# teensy_3-6sch.net
KiCad netlist of a schematic drawn in EAGLE
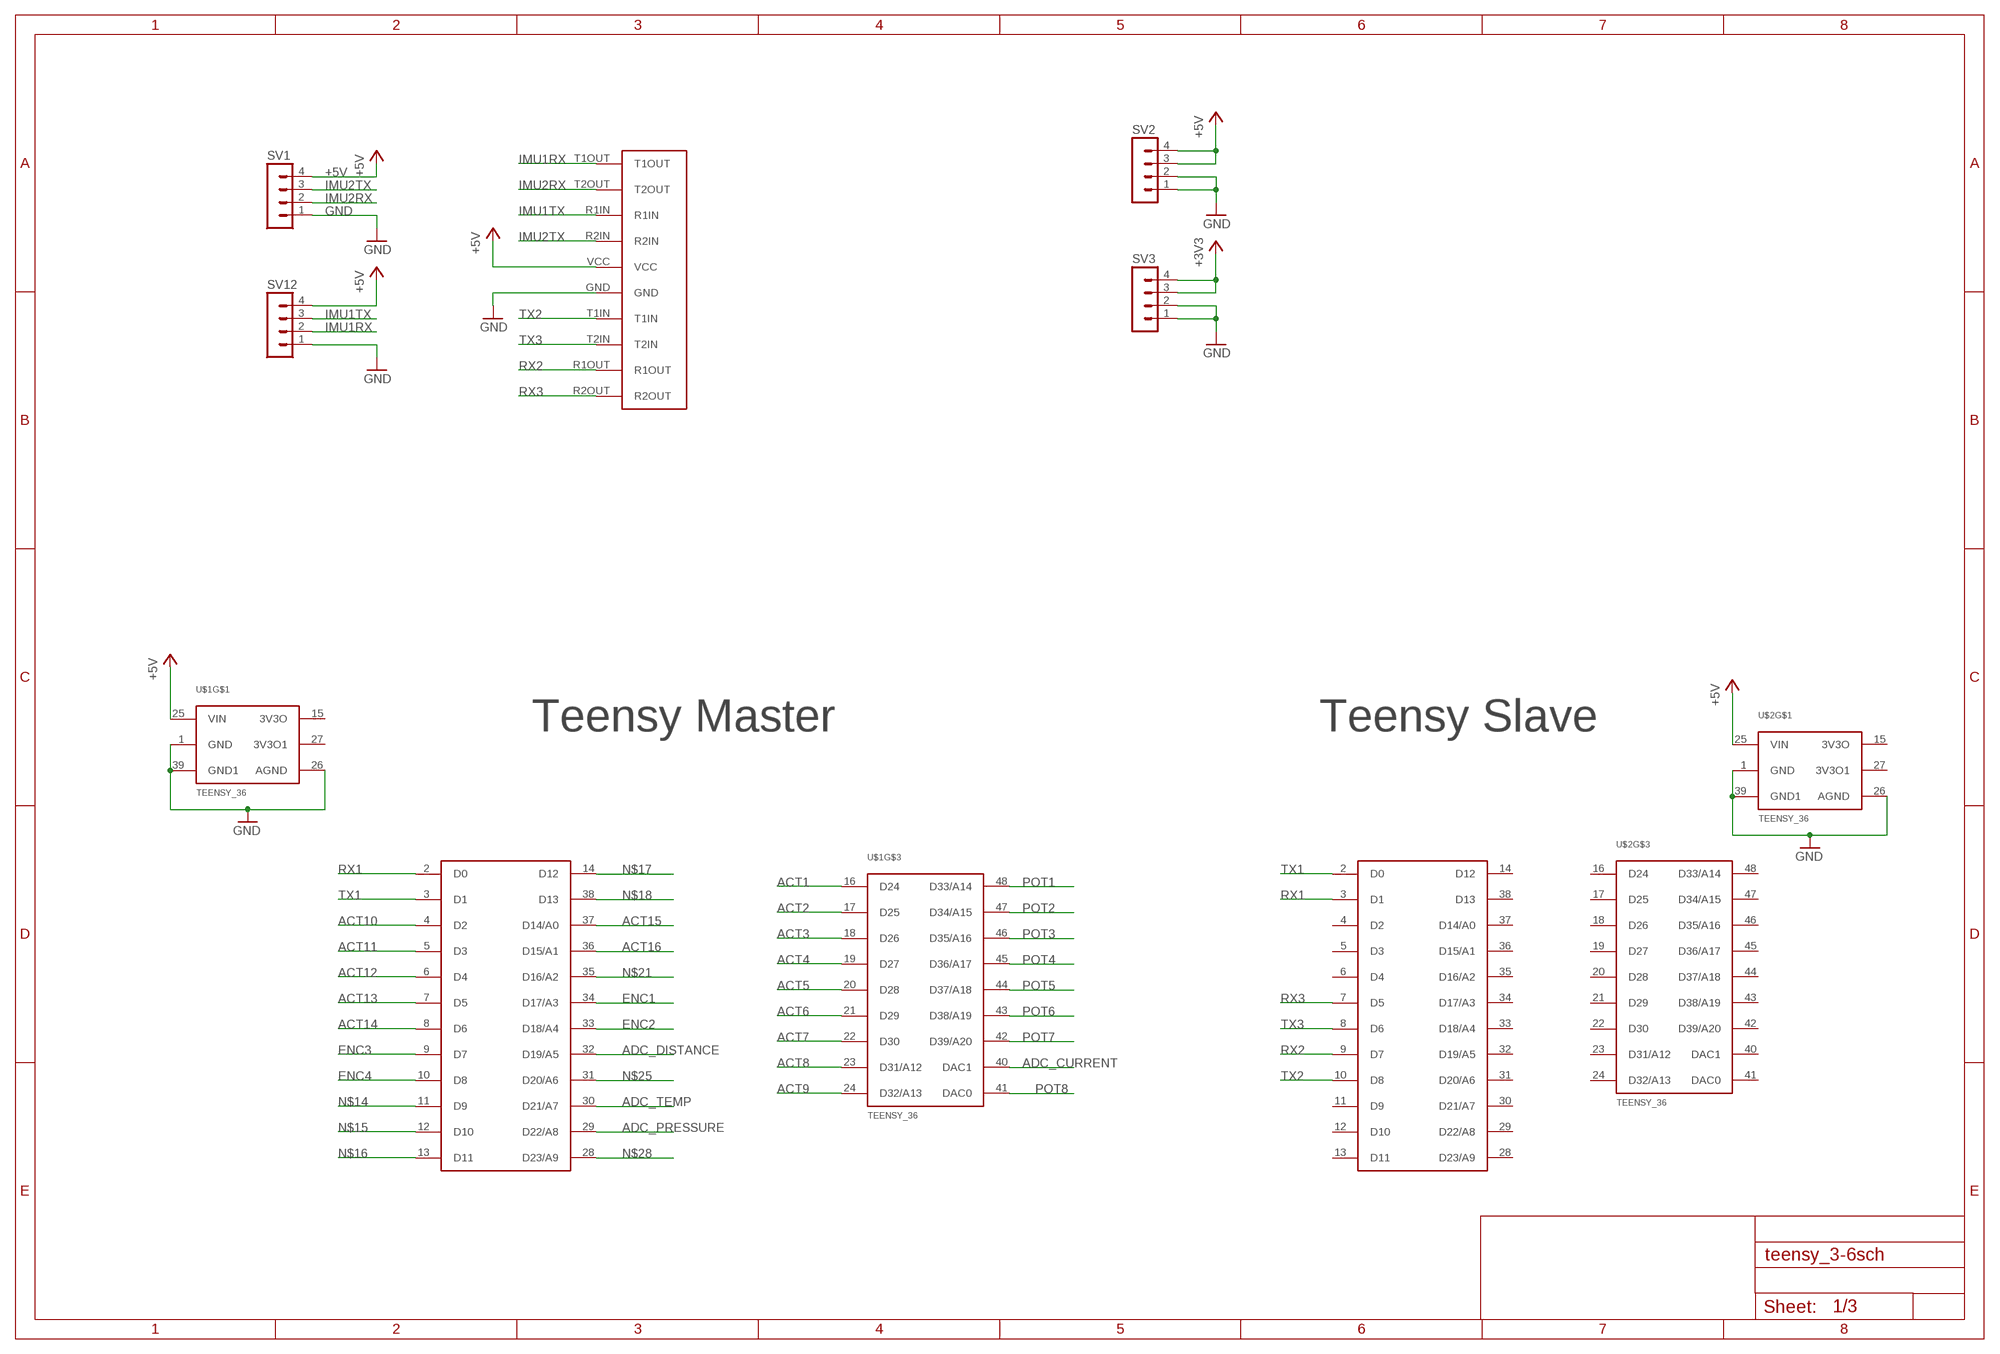
[diagram p0: schematic, sheet 1]
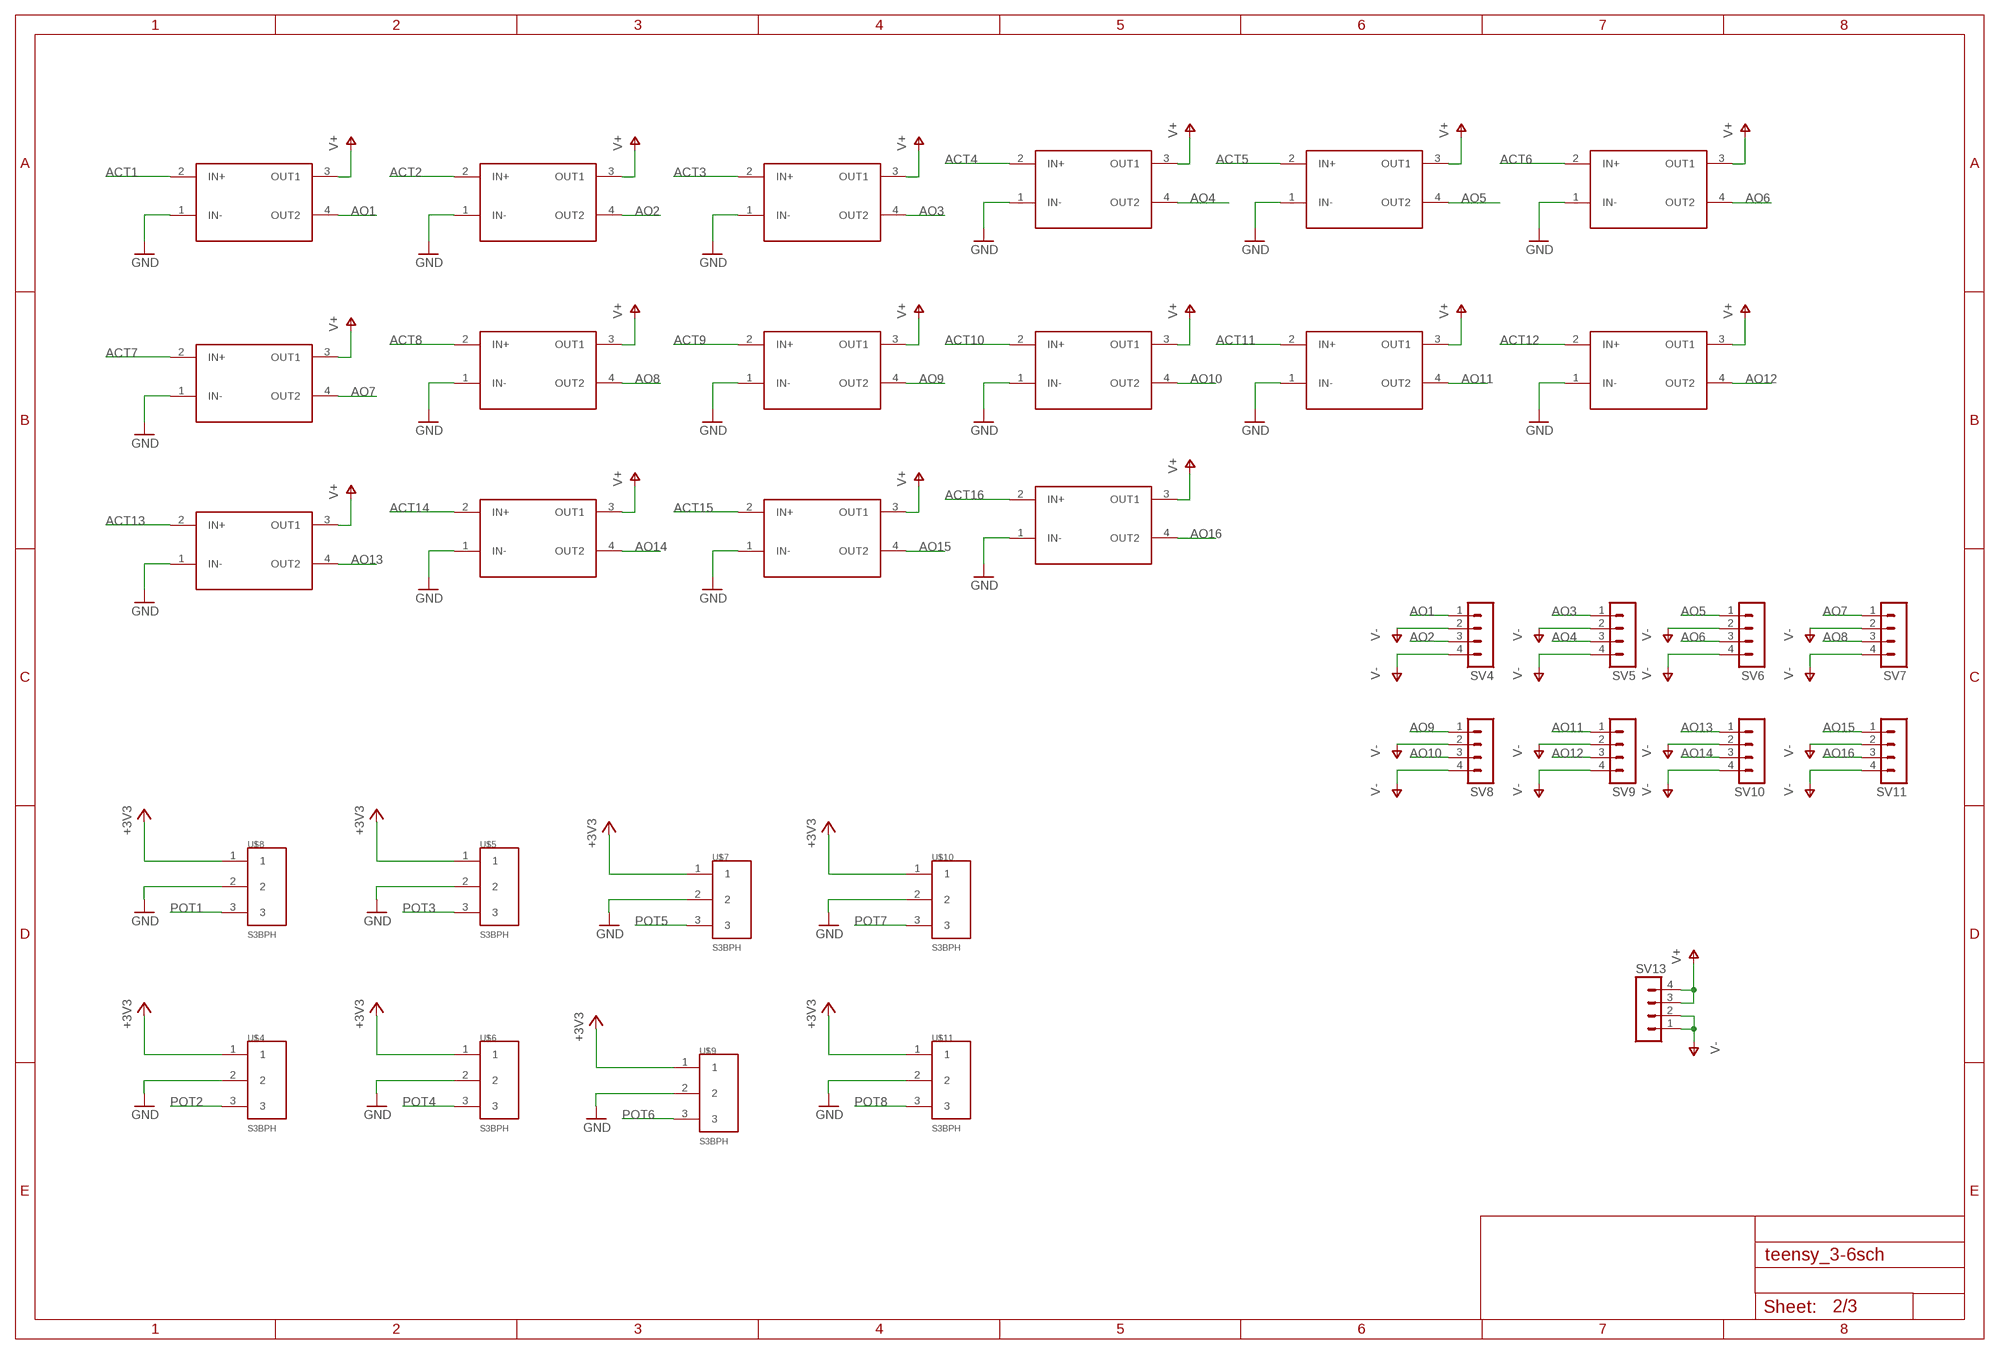
[diagram p1: schematic, sheet 2]
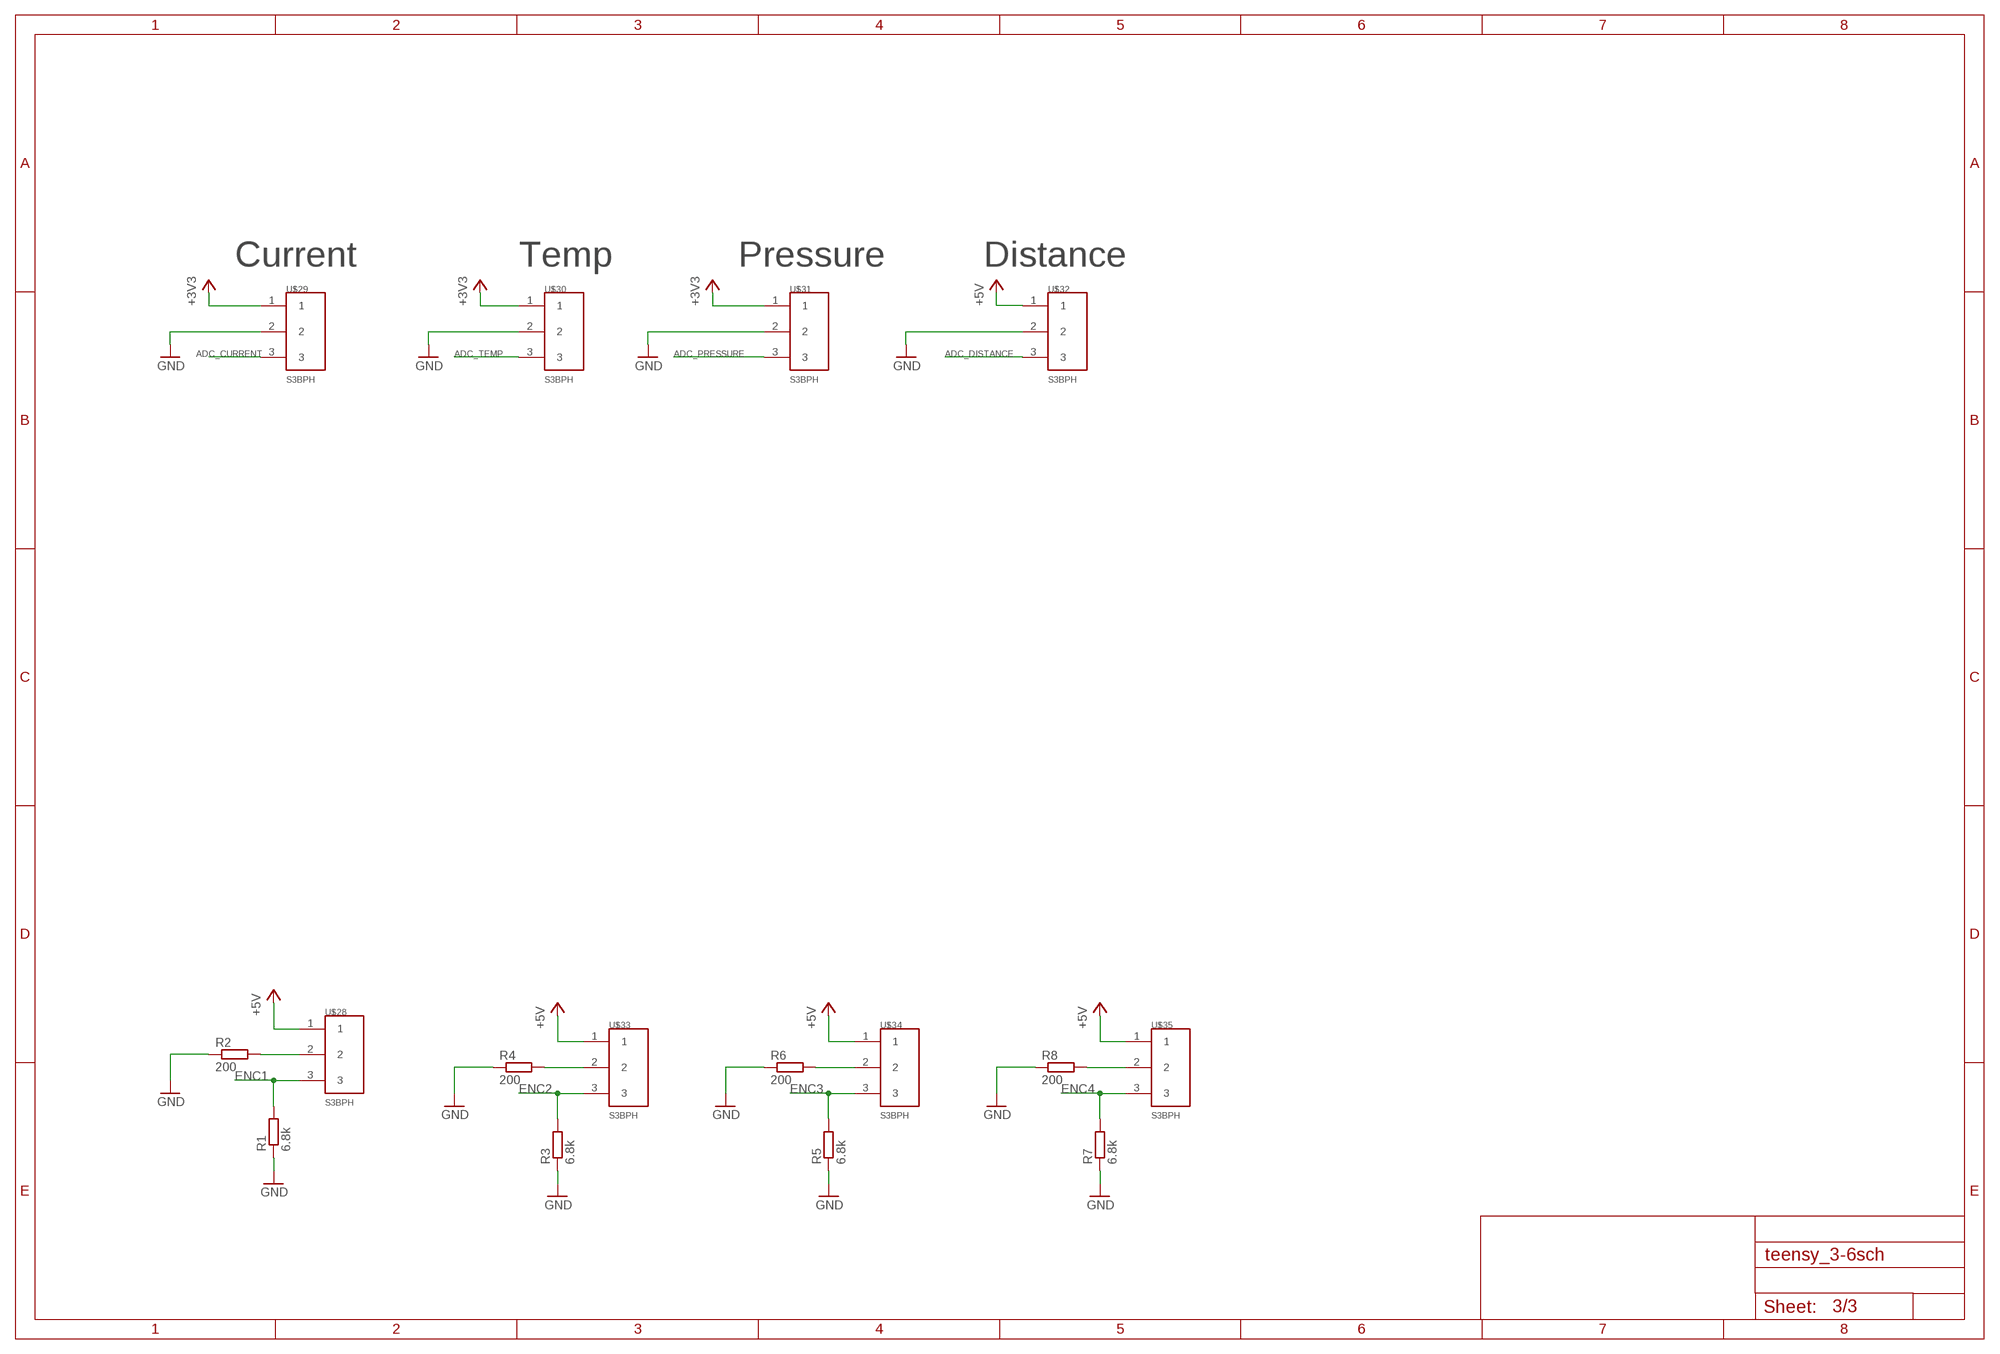
[diagram p2: schematic, sheet 3]

(export (version "E")
  (design (tool "Eeschema 10.0.6"))
  (components
    (comp (ref "SV1")
      (value "MA04-1")
      (footprint "eagle-import:MA04-1")
      (libsource (lib "eagle-import") (part "MA04-1"))
    )
    (comp (ref "SV2")
      (value "MA04-1")
      (footprint "eagle-import:MA04-1")
      (libsource (lib "eagle-import") (part "MA04-1"))
    )
    (comp (ref "SV3")
      (value "MA04-1")
      (footprint "eagle-import:MA04-1")
      (libsource (lib "eagle-import") (part "MA04-1"))
    )
    (comp (ref "SV12")
      (value "MA04-1")
      (footprint "eagle-import:MA04-1")
      (libsource (lib "eagle-import") (part "MA04-1"))
    )
    (comp (ref "U$1")
      (value "TEENSY_36")
      (footprint "eagle-import:TEENSY36")
      (libsource (lib "eagle-import") (part "TEENSY_36"))
    )
    (comp (ref "U$2")
      (value "TEENSY_36")
      (footprint "eagle-import:TEENSY36")
      (libsource (lib "eagle-import") (part "TEENSY_36"))
    )
    (comp (ref "U$3")
      (value "MAX232_BREAKOUT")
      (footprint "eagle-import:MAX232_BREAKOUT")
      (libsource (lib "eagle-import") (part "MAX232_BREAKOUT"))
    )
    (comp (ref "R1")
      (value "6.8k")
      (footprint "eagle-import:M0805")
      (libsource (lib "eagle-import") (part "R-EU_M0805"))
    )
    (comp (ref "R2")
      (value "200")
      (footprint "eagle-import:M0805")
      (libsource (lib "eagle-import") (part "R-EU_M0805"))
    )
    (comp (ref "R3")
      (value "6.8k")
      (footprint "eagle-import:M0805")
      (libsource (lib "eagle-import") (part "R-EU_M0805"))
    )
    (comp (ref "R4")
      (value "200")
      (footprint "eagle-import:M0805")
      (libsource (lib "eagle-import") (part "R-EU_M0805"))
    )
    (comp (ref "R5")
      (value "6.8k")
      (footprint "eagle-import:M0805")
      (libsource (lib "eagle-import") (part "R-EU_M0805"))
    )
    (comp (ref "R6")
      (value "200")
      (footprint "eagle-import:M0805")
      (libsource (lib "eagle-import") (part "R-EU_M0805"))
    )
    (comp (ref "R7")
      (value "6.8k")
      (footprint "eagle-import:M0805")
      (libsource (lib "eagle-import") (part "R-EU_M0805"))
    )
    (comp (ref "R8")
      (value "200")
      (footprint "eagle-import:M0805")
      (libsource (lib "eagle-import") (part "R-EU_M0805"))
    )
    (comp (ref "U$28")
      (value "S3BPH")
      (footprint "eagle-import:S3BPH")
      (libsource (lib "eagle-import") (part "S3BPH"))
    )
    (comp (ref "U$29")
      (value "S3BPH")
      (footprint "eagle-import:S3BPH")
      (libsource (lib "eagle-import") (part "S3BPH"))
    )
    (comp (ref "U$30")
      (value "S3BPH")
      (footprint "eagle-import:S3BPH")
      (libsource (lib "eagle-import") (part "S3BPH"))
    )
    (comp (ref "U$31")
      (value "S3BPH")
      (footprint "eagle-import:S3BPH")
      (libsource (lib "eagle-import") (part "S3BPH"))
    )
    (comp (ref "U$32")
      (value "S3BPH")
      (footprint "eagle-import:S3BPH")
      (libsource (lib "eagle-import") (part "S3BPH"))
    )
    (comp (ref "U$33")
      (value "S3BPH")
      (footprint "eagle-import:S3BPH")
      (libsource (lib "eagle-import") (part "S3BPH"))
    )
    (comp (ref "U$34")
      (value "S3BPH")
      (footprint "eagle-import:S3BPH")
      (libsource (lib "eagle-import") (part "S3BPH"))
    )
    (comp (ref "U$35")
      (value "S3BPH")
      (footprint "eagle-import:S3BPH")
      (libsource (lib "eagle-import") (part "S3BPH"))
    )
    (comp (ref "SV4")
      (value "MA04-1")
      (footprint "eagle-import:MA04-1")
      (libsource (lib "eagle-import") (part "MA04-1"))
    )
    (comp (ref "SV5")
      (value "MA04-1")
      (footprint "eagle-import:MA04-1")
      (libsource (lib "eagle-import") (part "MA04-1"))
    )
    (comp (ref "SV6")
      (value "MA04-1")
      (footprint "eagle-import:MA04-1")
      (libsource (lib "eagle-import") (part "MA04-1"))
    )
    (comp (ref "SV7")
      (value "MA04-1")
      (footprint "eagle-import:MA04-1")
      (libsource (lib "eagle-import") (part "MA04-1"))
    )
    (comp (ref "SV8")
      (value "MA04-1")
      (footprint "eagle-import:MA04-1")
      (libsource (lib "eagle-import") (part "MA04-1"))
    )
    (comp (ref "SV9")
      (value "MA04-1")
      (footprint "eagle-import:MA04-1")
      (libsource (lib "eagle-import") (part "MA04-1"))
    )
    (comp (ref "SV10")
      (value "MA04-1")
      (footprint "eagle-import:MA04-1")
      (libsource (lib "eagle-import") (part "MA04-1"))
    )
    (comp (ref "SV11")
      (value "MA04-1")
      (footprint "eagle-import:MA04-1")
      (libsource (lib "eagle-import") (part "MA04-1"))
    )
    (comp (ref "SV13")
      (value "MA04-1")
      (footprint "eagle-import:MA04-1")
      (libsource (lib "eagle-import") (part "MA04-1"))
    )
    (comp (ref "U$4")
      (value "S3BPH")
      (footprint "eagle-import:S3BPH")
      (libsource (lib "eagle-import") (part "S3BPH"))
    )
    (comp (ref "U$5")
      (value "S3BPH")
      (footprint "eagle-import:S3BPH")
      (libsource (lib "eagle-import") (part "S3BPH"))
    )
    (comp (ref "U$6")
      (value "S3BPH")
      (footprint "eagle-import:S3BPH")
      (libsource (lib "eagle-import") (part "S3BPH"))
    )
    (comp (ref "U$7")
      (value "S3BPH")
      (footprint "eagle-import:S3BPH")
      (libsource (lib "eagle-import") (part "S3BPH"))
    )
    (comp (ref "U$8")
      (value "S3BPH")
      (footprint "eagle-import:S3BPH")
      (libsource (lib "eagle-import") (part "S3BPH"))
    )
    (comp (ref "U$9")
      (value "S3BPH")
      (footprint "eagle-import:S3BPH")
      (libsource (lib "eagle-import") (part "S3BPH"))
    )
    (comp (ref "U$10")
      (value "S3BPH")
      (footprint "eagle-import:S3BPH")
      (libsource (lib "eagle-import") (part "S3BPH"))
    )
    (comp (ref "U$11")
      (value "S3BPH")
      (footprint "eagle-import:S3BPH")
      (libsource (lib "eagle-import") (part "S3BPH"))
    )
    (comp (ref "U$12")
      (value "CPC1706")
      (footprint "eagle-import:CPC1706")
      (libsource (lib "eagle-import") (part "CPC1706"))
    )
    (comp (ref "U$13")
      (value "CPC1706")
      (footprint "eagle-import:CPC1706")
      (libsource (lib "eagle-import") (part "CPC1706"))
    )
    (comp (ref "U$14")
      (value "CPC1706")
      (footprint "eagle-import:CPC1706")
      (libsource (lib "eagle-import") (part "CPC1706"))
    )
    (comp (ref "U$15")
      (value "CPC1706")
      (footprint "eagle-import:CPC1706")
      (libsource (lib "eagle-import") (part "CPC1706"))
    )
    (comp (ref "U$16")
      (value "CPC1706")
      (footprint "eagle-import:CPC1706")
      (libsource (lib "eagle-import") (part "CPC1706"))
    )
    (comp (ref "U$17")
      (value "CPC1706")
      (footprint "eagle-import:CPC1706")
      (libsource (lib "eagle-import") (part "CPC1706"))
    )
    (comp (ref "U$18")
      (value "CPC1706")
      (footprint "eagle-import:CPC1706")
      (libsource (lib "eagle-import") (part "CPC1706"))
    )
    (comp (ref "U$19")
      (value "CPC1706")
      (footprint "eagle-import:CPC1706")
      (libsource (lib "eagle-import") (part "CPC1706"))
    )
    (comp (ref "U$20")
      (value "CPC1706")
      (footprint "eagle-import:CPC1706")
      (libsource (lib "eagle-import") (part "CPC1706"))
    )
    (comp (ref "U$21")
      (value "CPC1706")
      (footprint "eagle-import:CPC1706")
      (libsource (lib "eagle-import") (part "CPC1706"))
    )
    (comp (ref "U$22")
      (value "CPC1706")
      (footprint "eagle-import:CPC1706")
      (libsource (lib "eagle-import") (part "CPC1706"))
    )
    (comp (ref "U$23")
      (value "CPC1706")
      (footprint "eagle-import:CPC1706")
      (libsource (lib "eagle-import") (part "CPC1706"))
    )
    (comp (ref "U$24")
      (value "CPC1706")
      (footprint "eagle-import:CPC1706")
      (libsource (lib "eagle-import") (part "CPC1706"))
    )
    (comp (ref "U$25")
      (value "CPC1706")
      (footprint "eagle-import:CPC1706")
      (libsource (lib "eagle-import") (part "CPC1706"))
    )
    (comp (ref "U$26")
      (value "CPC1706")
      (footprint "eagle-import:CPC1706")
      (libsource (lib "eagle-import") (part "CPC1706"))
    )
    (comp (ref "U$27")
      (value "CPC1706")
      (footprint "eagle-import:CPC1706")
      (libsource (lib "eagle-import") (part "CPC1706"))
    )
  )
  (nets
    (net (code "1") (name "+3V3") (class "Default")
      (node (ref "SV3") (pin "3") (pinfunction "3_3") (pintype "passive"))
      (node (ref "SV3") (pin "4") (pinfunction "4_4") (pintype "passive"))
      (node (ref "U$10") (pin "1") (pinfunction "1_1") (pintype "bidirectional"))
      (node (ref "U$11") (pin "1") (pinfunction "1_1") (pintype "bidirectional"))
      (node (ref "U$29") (pin "1") (pinfunction "1_1") (pintype "bidirectional"))
      (node (ref "U$30") (pin "1") (pinfunction "1_1") (pintype "bidirectional"))
      (node (ref "U$31") (pin "1") (pinfunction "1_1") (pintype "bidirectional"))
      (node (ref "U$4") (pin "1") (pinfunction "1_1") (pintype "bidirectional"))
      (node (ref "U$5") (pin "1") (pinfunction "1_1") (pintype "bidirectional"))
      (node (ref "U$6") (pin "1") (pinfunction "1_1") (pintype "bidirectional"))
      (node (ref "U$7") (pin "1") (pinfunction "1_1") (pintype "bidirectional"))
      (node (ref "U$8") (pin "1") (pinfunction "1_1") (pintype "bidirectional"))
      (node (ref "U$9") (pin "1") (pinfunction "1_1") (pintype "bidirectional"))
    )
    (net (code "2") (name "+5V") (class "Default")
      (node (ref "SV1") (pin "4") (pinfunction "4_4") (pintype "passive"))
      (node (ref "SV12") (pin "4") (pinfunction "4_4") (pintype "passive"))
      (node (ref "SV2") (pin "3") (pinfunction "3_3") (pintype "passive"))
      (node (ref "SV2") (pin "4") (pinfunction "4_4") (pintype "passive"))
      (node (ref "U$1") (pin "25") (pinfunction "VIN_25") (pintype "bidirectional"))
      (node (ref "U$2") (pin "25") (pinfunction "VIN_25") (pintype "bidirectional"))
      (node (ref "U$28") (pin "1") (pinfunction "1_1") (pintype "bidirectional"))
      (node (ref "U$3") (pin "VCC") (pinfunction "VCC_VCC") (pintype "bidirectional"))
      (node (ref "U$32") (pin "1") (pinfunction "1_1") (pintype "bidirectional"))
      (node (ref "U$33") (pin "1") (pinfunction "1_1") (pintype "bidirectional"))
      (node (ref "U$34") (pin "1") (pinfunction "1_1") (pintype "bidirectional"))
      (node (ref "U$35") (pin "1") (pinfunction "1_1") (pintype "bidirectional"))
    )
    (net (code "3") (name "ACT1") (class "Default")
      (node (ref "U$1") (pin "16") (pinfunction "D24_16") (pintype "bidirectional"))
      (node (ref "U$12") (pin "2") (pinfunction "IN+_2") (pintype "bidirectional"))
    )
    (net (code "4") (name "ACT2") (class "Default")
      (node (ref "U$1") (pin "17") (pinfunction "D25_17") (pintype "bidirectional"))
      (node (ref "U$13") (pin "2") (pinfunction "IN+_2") (pintype "bidirectional"))
    )
    (net (code "5") (name "ACT3") (class "Default")
      (node (ref "U$1") (pin "18") (pinfunction "D26_18") (pintype "bidirectional"))
      (node (ref "U$14") (pin "2") (pinfunction "IN+_2") (pintype "bidirectional"))
    )
    (net (code "6") (name "ACT4") (class "Default")
      (node (ref "U$1") (pin "19") (pinfunction "D27_19") (pintype "bidirectional"))
      (node (ref "U$15") (pin "2") (pinfunction "IN+_2") (pintype "bidirectional"))
    )
    (net (code "7") (name "ACT5") (class "Default")
      (node (ref "U$1") (pin "20") (pinfunction "D28_20") (pintype "bidirectional"))
      (node (ref "U$16") (pin "2") (pinfunction "IN+_2") (pintype "bidirectional"))
    )
    (net (code "8") (name "ACT6") (class "Default")
      (node (ref "U$1") (pin "21") (pinfunction "D29_21") (pintype "bidirectional"))
      (node (ref "U$17") (pin "2") (pinfunction "IN+_2") (pintype "bidirectional"))
    )
    (net (code "9") (name "ACT7") (class "Default")
      (node (ref "U$1") (pin "22") (pinfunction "D30_22") (pintype "bidirectional"))
      (node (ref "U$18") (pin "2") (pinfunction "IN+_2") (pintype "bidirectional"))
    )
    (net (code "10") (name "ACT8") (class "Default")
      (node (ref "U$1") (pin "23") (pinfunction "D31/A12_23") (pintype "bidirectional"))
      (node (ref "U$19") (pin "2") (pinfunction "IN+_2") (pintype "bidirectional"))
    )
    (net (code "11") (name "ACT9") (class "Default")
      (node (ref "U$1") (pin "24") (pinfunction "D32/A13_24") (pintype "bidirectional"))
      (node (ref "U$20") (pin "2") (pinfunction "IN+_2") (pintype "bidirectional"))
    )
    (net (code "12") (name "ACT10") (class "Default")
      (node (ref "U$1") (pin "4") (pinfunction "D2_4") (pintype "bidirectional"))
      (node (ref "U$21") (pin "2") (pinfunction "IN+_2") (pintype "bidirectional"))
    )
    (net (code "13") (name "ACT11") (class "Default")
      (node (ref "U$1") (pin "5") (pinfunction "D3_5") (pintype "bidirectional"))
      (node (ref "U$22") (pin "2") (pinfunction "IN+_2") (pintype "bidirectional"))
    )
    (net (code "14") (name "ACT12") (class "Default")
      (node (ref "U$1") (pin "6") (pinfunction "D4_6") (pintype "bidirectional"))
      (node (ref "U$23") (pin "2") (pinfunction "IN+_2") (pintype "bidirectional"))
    )
    (net (code "15") (name "ACT13") (class "Default")
      (node (ref "U$1") (pin "7") (pinfunction "D5_7") (pintype "bidirectional"))
      (node (ref "U$24") (pin "2") (pinfunction "IN+_2") (pintype "bidirectional"))
    )
    (net (code "16") (name "ACT14") (class "Default")
      (node (ref "U$1") (pin "8") (pinfunction "D6_8") (pintype "bidirectional"))
      (node (ref "U$25") (pin "2") (pinfunction "IN+_2") (pintype "bidirectional"))
    )
    (net (code "17") (name "ACT15") (class "Default")
      (node (ref "U$1") (pin "37") (pinfunction "D14/A0_37") (pintype "bidirectional"))
      (node (ref "U$26") (pin "2") (pinfunction "IN+_2") (pintype "bidirectional"))
    )
    (net (code "18") (name "ACT16") (class "Default")
      (node (ref "U$1") (pin "36") (pinfunction "D15/A1_36") (pintype "bidirectional"))
      (node (ref "U$27") (pin "2") (pinfunction "IN+_2") (pintype "bidirectional"))
    )
    (net (code "19") (name "ADC_CURRENT") (class "Default")
      (node (ref "U$1") (pin "40") (pinfunction "DAC1_40") (pintype "bidirectional"))
      (node (ref "U$29") (pin "3") (pinfunction "3_3") (pintype "bidirectional"))
    )
    (net (code "20") (name "ADC_DISTANCE") (class "Default")
      (node (ref "U$1") (pin "32") (pinfunction "D19/A5_32") (pintype "bidirectional"))
      (node (ref "U$32") (pin "3") (pinfunction "3_3") (pintype "bidirectional"))
    )
    (net (code "21") (name "ADC_PRESSURE") (class "Default")
      (node (ref "U$1") (pin "29") (pinfunction "D22/A8_29") (pintype "bidirectional"))
      (node (ref "U$31") (pin "3") (pinfunction "3_3") (pintype "bidirectional"))
    )
    (net (code "22") (name "ADC_TEMP") (class "Default")
      (node (ref "U$1") (pin "30") (pinfunction "D21/A7_30") (pintype "bidirectional"))
      (node (ref "U$30") (pin "3") (pinfunction "3_3") (pintype "bidirectional"))
    )
    (net (code "23") (name "AO1") (class "Default")
      (node (ref "SV4") (pin "1") (pinfunction "1_1") (pintype "passive"))
      (node (ref "U$12") (pin "4") (pinfunction "OUT2_4") (pintype "bidirectional"))
    )
    (net (code "24") (name "AO2") (class "Default")
      (node (ref "SV4") (pin "3") (pinfunction "3_3") (pintype "passive"))
      (node (ref "U$13") (pin "4") (pinfunction "OUT2_4") (pintype "bidirectional"))
    )
    (net (code "25") (name "AO3") (class "Default")
      (node (ref "SV5") (pin "1") (pinfunction "1_1") (pintype "passive"))
      (node (ref "U$14") (pin "4") (pinfunction "OUT2_4") (pintype "bidirectional"))
    )
    (net (code "26") (name "AO4") (class "Default")
      (node (ref "SV5") (pin "3") (pinfunction "3_3") (pintype "passive"))
      (node (ref "U$15") (pin "4") (pinfunction "OUT2_4") (pintype "bidirectional"))
    )
    (net (code "27") (name "AO5") (class "Default")
      (node (ref "SV6") (pin "1") (pinfunction "1_1") (pintype "passive"))
      (node (ref "U$16") (pin "4") (pinfunction "OUT2_4") (pintype "bidirectional"))
    )
    (net (code "28") (name "AO6") (class "Default")
      (node (ref "SV6") (pin "3") (pinfunction "3_3") (pintype "passive"))
      (node (ref "U$17") (pin "4") (pinfunction "OUT2_4") (pintype "bidirectional"))
    )
    (net (code "29") (name "AO7") (class "Default")
      (node (ref "SV7") (pin "1") (pinfunction "1_1") (pintype "passive"))
      (node (ref "U$18") (pin "4") (pinfunction "OUT2_4") (pintype "bidirectional"))
    )
    (net (code "30") (name "AO8") (class "Default")
      (node (ref "SV7") (pin "3") (pinfunction "3_3") (pintype "passive"))
      (node (ref "U$19") (pin "4") (pinfunction "OUT2_4") (pintype "bidirectional"))
    )
    (net (code "31") (name "AO9") (class "Default")
      (node (ref "SV8") (pin "1") (pinfunction "1_1") (pintype "passive"))
      (node (ref "U$20") (pin "4") (pinfunction "OUT2_4") (pintype "bidirectional"))
    )
    (net (code "32") (name "AO10") (class "Default")
      (node (ref "SV8") (pin "3") (pinfunction "3_3") (pintype "passive"))
      (node (ref "U$21") (pin "4") (pinfunction "OUT2_4") (pintype "bidirectional"))
    )
    (net (code "33") (name "AO11") (class "Default")
      (node (ref "SV9") (pin "1") (pinfunction "1_1") (pintype "passive"))
      (node (ref "U$22") (pin "4") (pinfunction "OUT2_4") (pintype "bidirectional"))
    )
    (net (code "34") (name "AO12") (class "Default")
      (node (ref "SV9") (pin "3") (pinfunction "3_3") (pintype "passive"))
      (node (ref "U$23") (pin "4") (pinfunction "OUT2_4") (pintype "bidirectional"))
    )
    (net (code "35") (name "AO13") (class "Default")
      (node (ref "SV10") (pin "1") (pinfunction "1_1") (pintype "passive"))
      (node (ref "U$24") (pin "4") (pinfunction "OUT2_4") (pintype "bidirectional"))
    )
    (net (code "36") (name "AO14") (class "Default")
      (node (ref "SV10") (pin "3") (pinfunction "3_3") (pintype "passive"))
      (node (ref "U$25") (pin "4") (pinfunction "OUT2_4") (pintype "bidirectional"))
    )
    (net (code "37") (name "AO15") (class "Default")
      (node (ref "SV11") (pin "1") (pinfunction "1_1") (pintype "passive"))
      (node (ref "U$26") (pin "4") (pinfunction "OUT2_4") (pintype "bidirectional"))
    )
    (net (code "38") (name "AO16") (class "Default")
      (node (ref "SV11") (pin "3") (pinfunction "3_3") (pintype "passive"))
      (node (ref "U$27") (pin "4") (pinfunction "OUT2_4") (pintype "bidirectional"))
    )
    (net (code "39") (name "ENC1") (class "Default")
      (node (ref "R1") (pin "2") (pinfunction "2_2") (pintype "passive"))
      (node (ref "U$1") (pin "34") (pinfunction "D17/A3_34") (pintype "bidirectional"))
      (node (ref "U$28") (pin "3") (pinfunction "3_3") (pintype "bidirectional"))
    )
    (net (code "40") (name "ENC2") (class "Default")
      (node (ref "R3") (pin "2") (pinfunction "2_2") (pintype "passive"))
      (node (ref "U$1") (pin "33") (pinfunction "D18/A4_33") (pintype "bidirectional"))
      (node (ref "U$33") (pin "3") (pinfunction "3_3") (pintype "bidirectional"))
    )
    (net (code "41") (name "ENC3") (class "Default")
      (node (ref "R5") (pin "2") (pinfunction "2_2") (pintype "passive"))
      (node (ref "U$1") (pin "9") (pinfunction "D7_9") (pintype "bidirectional"))
      (node (ref "U$34") (pin "3") (pinfunction "3_3") (pintype "bidirectional"))
    )
    (net (code "42") (name "ENC4") (class "Default")
      (node (ref "R7") (pin "2") (pinfunction "2_2") (pintype "passive"))
      (node (ref "U$1") (pin "10") (pinfunction "D8_10") (pintype "bidirectional"))
      (node (ref "U$35") (pin "3") (pinfunction "3_3") (pintype "bidirectional"))
    )
    (net (code "43") (name "GND") (class "Default")
      (node (ref "R1") (pin "1") (pinfunction "1_1") (pintype "passive"))
      (node (ref "R2") (pin "1") (pinfunction "1_1") (pintype "passive"))
      (node (ref "R3") (pin "1") (pinfunction "1_1") (pintype "passive"))
      (node (ref "R4") (pin "1") (pinfunction "1_1") (pintype "passive"))
      (node (ref "R5") (pin "1") (pinfunction "1_1") (pintype "passive"))
      (node (ref "R6") (pin "1") (pinfunction "1_1") (pintype "passive"))
      (node (ref "R7") (pin "1") (pinfunction "1_1") (pintype "passive"))
      (node (ref "R8") (pin "1") (pinfunction "1_1") (pintype "passive"))
      (node (ref "SV1") (pin "1") (pinfunction "1_1") (pintype "passive"))
      (node (ref "SV12") (pin "1") (pinfunction "1_1") (pintype "passive"))
      (node (ref "SV2") (pin "1") (pinfunction "1_1") (pintype "passive"))
      (node (ref "SV2") (pin "2") (pinfunction "2_2") (pintype "passive"))
      (node (ref "SV3") (pin "1") (pinfunction "1_1") (pintype "passive"))
      (node (ref "SV3") (pin "2") (pinfunction "2_2") (pintype "passive"))
      (node (ref "U$1") (pin "1") (pinfunction "GND_1") (pintype "bidirectional"))
      (node (ref "U$1") (pin "26") (pinfunction "AGND_26") (pintype "bidirectional"))
      (node (ref "U$1") (pin "39") (pinfunction "GND1_39") (pintype "bidirectional"))
      (node (ref "U$10") (pin "2") (pinfunction "2_2") (pintype "bidirectional"))
      (node (ref "U$11") (pin "2") (pinfunction "2_2") (pintype "bidirectional"))
      (node (ref "U$12") (pin "1") (pinfunction "IN-_1") (pintype "bidirectional"))
      (node (ref "U$13") (pin "1") (pinfunction "IN-_1") (pintype "bidirectional"))
      (node (ref "U$14") (pin "1") (pinfunction "IN-_1") (pintype "bidirectional"))
      (node (ref "U$15") (pin "1") (pinfunction "IN-_1") (pintype "bidirectional"))
      (node (ref "U$16") (pin "1") (pinfunction "IN-_1") (pintype "bidirectional"))
      (node (ref "U$17") (pin "1") (pinfunction "IN-_1") (pintype "bidirectional"))
      (node (ref "U$18") (pin "1") (pinfunction "IN-_1") (pintype "bidirectional"))
      (node (ref "U$19") (pin "1") (pinfunction "IN-_1") (pintype "bidirectional"))
      (node (ref "U$2") (pin "1") (pinfunction "GND_1") (pintype "bidirectional"))
      (node (ref "U$2") (pin "26") (pinfunction "AGND_26") (pintype "bidirectional"))
      (node (ref "U$2") (pin "39") (pinfunction "GND1_39") (pintype "bidirectional"))
      (node (ref "U$20") (pin "1") (pinfunction "IN-_1") (pintype "bidirectional"))
      (node (ref "U$21") (pin "1") (pinfunction "IN-_1") (pintype "bidirectional"))
      (node (ref "U$22") (pin "1") (pinfunction "IN-_1") (pintype "bidirectional"))
      (node (ref "U$23") (pin "1") (pinfunction "IN-_1") (pintype "bidirectional"))
      (node (ref "U$24") (pin "1") (pinfunction "IN-_1") (pintype "bidirectional"))
      (node (ref "U$25") (pin "1") (pinfunction "IN-_1") (pintype "bidirectional"))
      (node (ref "U$26") (pin "1") (pinfunction "IN-_1") (pintype "bidirectional"))
      (node (ref "U$27") (pin "1") (pinfunction "IN-_1") (pintype "bidirectional"))
      (node (ref "U$29") (pin "2") (pinfunction "2_2") (pintype "bidirectional"))
      (node (ref "U$3") (pin "GND") (pinfunction "GND_GND") (pintype "bidirectional"))
      (node (ref "U$30") (pin "2") (pinfunction "2_2") (pintype "bidirectional"))
      (node (ref "U$31") (pin "2") (pinfunction "2_2") (pintype "bidirectional"))
      (node (ref "U$32") (pin "2") (pinfunction "2_2") (pintype "bidirectional"))
      (node (ref "U$4") (pin "2") (pinfunction "2_2") (pintype "bidirectional"))
      (node (ref "U$5") (pin "2") (pinfunction "2_2") (pintype "bidirectional"))
      (node (ref "U$6") (pin "2") (pinfunction "2_2") (pintype "bidirectional"))
      (node (ref "U$7") (pin "2") (pinfunction "2_2") (pintype "bidirectional"))
      (node (ref "U$8") (pin "2") (pinfunction "2_2") (pintype "bidirectional"))
      (node (ref "U$9") (pin "2") (pinfunction "2_2") (pintype "bidirectional"))
    )
    (net (code "44") (name "IMU1RX") (class "Default")
      (node (ref "SV12") (pin "2") (pinfunction "2_2") (pintype "passive"))
      (node (ref "U$3") (pin "T1OUT") (pinfunction "T1OUT_T1OUT") (pintype "bidirectional"))
    )
    (net (code "45") (name "IMU1TX") (class "Default")
      (node (ref "SV12") (pin "3") (pinfunction "3_3") (pintype "passive"))
      (node (ref "U$3") (pin "R1IN") (pinfunction "R1IN_R1IN") (pintype "bidirectional"))
    )
    (net (code "46") (name "IMU2RX") (class "Default")
      (node (ref "SV1") (pin "2") (pinfunction "2_2") (pintype "passive"))
      (node (ref "U$3") (pin "T2OUT") (pinfunction "T2OUT_T2OUT") (pintype "bidirectional"))
    )
    (net (code "47") (name "IMU2TX") (class "Default")
      (node (ref "SV1") (pin "3") (pinfunction "3_3") (pintype "passive"))
      (node (ref "U$3") (pin "R2IN") (pinfunction "R2IN_R2IN") (pintype "bidirectional"))
    )
    (net (code "48") (name "N$14") (class "Default")
      (node (ref "U$1") (pin "11") (pinfunction "D9_11") (pintype "bidirectional"))
    )
    (net (code "49") (name "N$15") (class "Default")
      (node (ref "U$1") (pin "12") (pinfunction "D10_12") (pintype "bidirectional"))
    )
    (net (code "50") (name "N$16") (class "Default")
      (node (ref "U$1") (pin "13") (pinfunction "D11_13") (pintype "bidirectional"))
    )
    (net (code "51") (name "N$17") (class "Default")
      (node (ref "U$1") (pin "14") (pinfunction "D12_14") (pintype "bidirectional"))
    )
    (net (code "52") (name "N$18") (class "Default")
      (node (ref "U$1") (pin "38") (pinfunction "D13_38") (pintype "bidirectional"))
    )
    (net (code "53") (name "N$21") (class "Default")
      (node (ref "U$1") (pin "35") (pinfunction "D16/A2_35") (pintype "bidirectional"))
    )
    (net (code "54") (name "N$25") (class "Default")
      (node (ref "U$1") (pin "31") (pinfunction "D20/A6_31") (pintype "bidirectional"))
    )
    (net (code "55") (name "N$28") (class "Default")
      (node (ref "U$1") (pin "28") (pinfunction "D23/A9_28") (pintype "bidirectional"))
    )
    (net (code "56") (name "Net-(R2-Pad2)") (class "Default")
      (node (ref "R2") (pin "2") (pinfunction "2_2") (pintype "passive"))
      (node (ref "U$28") (pin "2") (pinfunction "2_2") (pintype "bidirectional"))
    )
    (net (code "57") (name "Net-(R4-Pad2)") (class "Default")
      (node (ref "R4") (pin "2") (pinfunction "2_2") (pintype "passive"))
      (node (ref "U$33") (pin "2") (pinfunction "2_2") (pintype "bidirectional"))
    )
    (net (code "58") (name "Net-(R6-Pad2)") (class "Default")
      (node (ref "R6") (pin "2") (pinfunction "2_2") (pintype "passive"))
      (node (ref "U$34") (pin "2") (pinfunction "2_2") (pintype "bidirectional"))
    )
    (net (code "59") (name "Net-(R8-Pad2)") (class "Default")
      (node (ref "R8") (pin "2") (pinfunction "2_2") (pintype "passive"))
      (node (ref "U$35") (pin "2") (pinfunction "2_2") (pintype "bidirectional"))
    )
    (net (code "60") (name "POT1") (class "Default")
      (node (ref "U$1") (pin "48") (pinfunction "D33/A14_48") (pintype "bidirectional"))
      (node (ref "U$8") (pin "3") (pinfunction "3_3") (pintype "bidirectional"))
    )
    (net (code "61") (name "POT2") (class "Default")
      (node (ref "U$1") (pin "47") (pinfunction "D34/A15_47") (pintype "bidirectional"))
      (node (ref "U$4") (pin "3") (pinfunction "3_3") (pintype "bidirectional"))
    )
    (net (code "62") (name "POT3") (class "Default")
      (node (ref "U$1") (pin "46") (pinfunction "D35/A16_46") (pintype "bidirectional"))
      (node (ref "U$5") (pin "3") (pinfunction "3_3") (pintype "bidirectional"))
    )
    (net (code "63") (name "POT4") (class "Default")
      (node (ref "U$1") (pin "45") (pinfunction "D36/A17_45") (pintype "bidirectional"))
      (node (ref "U$6") (pin "3") (pinfunction "3_3") (pintype "bidirectional"))
    )
    (net (code "64") (name "POT5") (class "Default")
      (node (ref "U$1") (pin "44") (pinfunction "D37/A18_44") (pintype "bidirectional"))
      (node (ref "U$7") (pin "3") (pinfunction "3_3") (pintype "bidirectional"))
    )
    (net (code "65") (name "POT6") (class "Default")
      (node (ref "U$1") (pin "43") (pinfunction "D38/A19_43") (pintype "bidirectional"))
      (node (ref "U$9") (pin "3") (pinfunction "3_3") (pintype "bidirectional"))
    )
    (net (code "66") (name "POT7") (class "Default")
      (node (ref "U$1") (pin "42") (pinfunction "D39/A20_42") (pintype "bidirectional"))
      (node (ref "U$10") (pin "3") (pinfunction "3_3") (pintype "bidirectional"))
    )
    (net (code "67") (name "POT8") (class "Default")
      (node (ref "U$1") (pin "41") (pinfunction "DAC0_41") (pintype "bidirectional"))
      (node (ref "U$11") (pin "3") (pinfunction "3_3") (pintype "bidirectional"))
    )
    (net (code "68") (name "RX1") (class "Default")
      (node (ref "U$1") (pin "2") (pinfunction "D0_2") (pintype "bidirectional"))
      (node (ref "U$2") (pin "3") (pinfunction "D1_3") (pintype "bidirectional"))
    )
    (net (code "69") (name "RX2") (class "Default")
      (node (ref "U$2") (pin "9") (pinfunction "D7_9") (pintype "bidirectional"))
      (node (ref "U$3") (pin "R1OUT") (pinfunction "R1OUT_R1OUT") (pintype "bidirectional"))
    )
    (net (code "70") (name "RX3") (class "Default")
      (node (ref "U$2") (pin "7") (pinfunction "D5_7") (pintype "bidirectional"))
      (node (ref "U$3") (pin "R2OUT") (pinfunction "R2OUT_R2OUT") (pintype "bidirectional"))
    )
    (net (code "71") (name "TX1") (class "Default")
      (node (ref "U$1") (pin "3") (pinfunction "D1_3") (pintype "bidirectional"))
      (node (ref "U$2") (pin "2") (pinfunction "D0_2") (pintype "bidirectional"))
    )
    (net (code "72") (name "TX2") (class "Default")
      (node (ref "U$2") (pin "10") (pinfunction "D8_10") (pintype "bidirectional"))
      (node (ref "U$3") (pin "T1IN") (pinfunction "T1IN_T1IN") (pintype "bidirectional"))
    )
    (net (code "73") (name "TX3") (class "Default")
      (node (ref "U$2") (pin "8") (pinfunction "D6_8") (pintype "bidirectional"))
      (node (ref "U$3") (pin "T2IN") (pinfunction "T2IN_T2IN") (pintype "bidirectional"))
    )
    (net (code "74") (name "V+") (class "Default")
      (node (ref "SV13") (pin "3") (pinfunction "3_3") (pintype "passive"))
      (node (ref "SV13") (pin "4") (pinfunction "4_4") (pintype "passive"))
      (node (ref "U$12") (pin "3") (pinfunction "OUT1_3") (pintype "bidirectional"))
      (node (ref "U$13") (pin "3") (pinfunction "OUT1_3") (pintype "bidirectional"))
      (node (ref "U$14") (pin "3") (pinfunction "OUT1_3") (pintype "bidirectional"))
      (node (ref "U$15") (pin "3") (pinfunction "OUT1_3") (pintype "bidirectional"))
      (node (ref "U$16") (pin "3") (pinfunction "OUT1_3") (pintype "bidirectional"))
      (node (ref "U$17") (pin "3") (pinfunction "OUT1_3") (pintype "bidirectional"))
      (node (ref "U$18") (pin "3") (pinfunction "OUT1_3") (pintype "bidirectional"))
      (node (ref "U$19") (pin "3") (pinfunction "OUT1_3") (pintype "bidirectional"))
      (node (ref "U$20") (pin "3") (pinfunction "OUT1_3") (pintype "bidirectional"))
      (node (ref "U$21") (pin "3") (pinfunction "OUT1_3") (pintype "bidirectional"))
      (node (ref "U$22") (pin "3") (pinfunction "OUT1_3") (pintype "bidirectional"))
      (node (ref "U$23") (pin "3") (pinfunction "OUT1_3") (pintype "bidirectional"))
      (node (ref "U$24") (pin "3") (pinfunction "OUT1_3") (pintype "bidirectional"))
      (node (ref "U$25") (pin "3") (pinfunction "OUT1_3") (pintype "bidirectional"))
      (node (ref "U$26") (pin "3") (pinfunction "OUT1_3") (pintype "bidirectional"))
      (node (ref "U$27") (pin "3") (pinfunction "OUT1_3") (pintype "bidirectional"))
    )
    (net (code "75") (name "V-") (class "Default")
      (node (ref "SV10") (pin "2") (pinfunction "2_2") (pintype "passive"))
      (node (ref "SV10") (pin "4") (pinfunction "4_4") (pintype "passive"))
      (node (ref "SV11") (pin "2") (pinfunction "2_2") (pintype "passive"))
      (node (ref "SV11") (pin "4") (pinfunction "4_4") (pintype "passive"))
      (node (ref "SV13") (pin "1") (pinfunction "1_1") (pintype "passive"))
      (node (ref "SV13") (pin "2") (pinfunction "2_2") (pintype "passive"))
      (node (ref "SV4") (pin "2") (pinfunction "2_2") (pintype "passive"))
      (node (ref "SV4") (pin "4") (pinfunction "4_4") (pintype "passive"))
      (node (ref "SV5") (pin "2") (pinfunction "2_2") (pintype "passive"))
      (node (ref "SV5") (pin "4") (pinfunction "4_4") (pintype "passive"))
      (node (ref "SV6") (pin "2") (pinfunction "2_2") (pintype "passive"))
      (node (ref "SV6") (pin "4") (pinfunction "4_4") (pintype "passive"))
      (node (ref "SV7") (pin "2") (pinfunction "2_2") (pintype "passive"))
      (node (ref "SV7") (pin "4") (pinfunction "4_4") (pintype "passive"))
      (node (ref "SV8") (pin "2") (pinfunction "2_2") (pintype "passive"))
      (node (ref "SV8") (pin "4") (pinfunction "4_4") (pintype "passive"))
      (node (ref "SV9") (pin "2") (pinfunction "2_2") (pintype "passive"))
      (node (ref "SV9") (pin "4") (pinfunction "4_4") (pintype "passive"))
    )
    (net (code "76") (name "unconnected-(U$1A-3V3O-Pad15)") (class "Default")
      (node (ref "U$1") (pin "15") (pinfunction "3V3O_15") (pintype "bidirectional"))
    )
    (net (code "77") (name "unconnected-(U$1A-3V3O1-Pad27)") (class "Default")
      (node (ref "U$1") (pin "27") (pinfunction "3V3O1_27") (pintype "bidirectional"))
    )
    (net (code "78") (name "unconnected-(U$2A-3V3O-Pad15)") (class "Default")
      (node (ref "U$2") (pin "15") (pinfunction "3V3O_15") (pintype "bidirectional"))
    )
    (net (code "79") (name "unconnected-(U$2A-3V3O1-Pad27)") (class "Default")
      (node (ref "U$2") (pin "27") (pinfunction "3V3O1_27") (pintype "bidirectional"))
    )
    (net (code "80") (name "unconnected-(U$2B-D2-Pad4)") (class "Default")
      (node (ref "U$2") (pin "4") (pinfunction "D2_4") (pintype "bidirectional"))
    )
    (net (code "81") (name "unconnected-(U$2B-D3-Pad5)") (class "Default")
      (node (ref "U$2") (pin "5") (pinfunction "D3_5") (pintype "bidirectional"))
    )
    (net (code "82") (name "unconnected-(U$2B-D4-Pad6)") (class "Default")
      (node (ref "U$2") (pin "6") (pinfunction "D4_6") (pintype "bidirectional"))
    )
    (net (code "83") (name "unconnected-(U$2B-D9-Pad11)") (class "Default")
      (node (ref "U$2") (pin "11") (pinfunction "D9_11") (pintype "bidirectional"))
    )
    (net (code "84") (name "unconnected-(U$2B-D10-Pad12)") (class "Default")
      (node (ref "U$2") (pin "12") (pinfunction "D10_12") (pintype "bidirectional"))
    )
    (net (code "85") (name "unconnected-(U$2B-D11-Pad13)") (class "Default")
      (node (ref "U$2") (pin "13") (pinfunction "D11_13") (pintype "bidirectional"))
    )
    (net (code "86") (name "unconnected-(U$2B-D12-Pad14)") (class "Default")
      (node (ref "U$2") (pin "14") (pinfunction "D12_14") (pintype "bidirectional"))
    )
    (net (code "87") (name "unconnected-(U$2B-D13-Pad38)") (class "Default")
      (node (ref "U$2") (pin "38") (pinfunction "D13_38") (pintype "bidirectional"))
    )
    (net (code "88") (name "unconnected-(U$2B-D14{slash}A0-Pad37)") (class "Default")
      (node (ref "U$2") (pin "37") (pinfunction "D14/A0_37") (pintype "bidirectional"))
    )
    (net (code "89") (name "unconnected-(U$2B-D15{slash}A1-Pad36)") (class "Default")
      (node (ref "U$2") (pin "36") (pinfunction "D15/A1_36") (pintype "bidirectional"))
    )
    (net (code "90") (name "unconnected-(U$2B-D16{slash}A2-Pad35)") (class "Default")
      (node (ref "U$2") (pin "35") (pinfunction "D16/A2_35") (pintype "bidirectional"))
    )
    (net (code "91") (name "unconnected-(U$2B-D17{slash}A3-Pad34)") (class "Default")
      (node (ref "U$2") (pin "34") (pinfunction "D17/A3_34") (pintype "bidirectional"))
    )
    (net (code "92") (name "unconnected-(U$2B-D18{slash}A4-Pad33)") (class "Default")
      (node (ref "U$2") (pin "33") (pinfunction "D18/A4_33") (pintype "bidirectional"))
    )
    (net (code "93") (name "unconnected-(U$2B-D19{slash}A5-Pad32)") (class "Default")
      (node (ref "U$2") (pin "32") (pinfunction "D19/A5_32") (pintype "bidirectional"))
    )
    (net (code "94") (name "unconnected-(U$2B-D20{slash}A6-Pad31)") (class "Default")
      (node (ref "U$2") (pin "31") (pinfunction "D20/A6_31") (pintype "bidirectional"))
    )
    (net (code "95") (name "unconnected-(U$2B-D21{slash}A7-Pad30)") (class "Default")
      (node (ref "U$2") (pin "30") (pinfunction "D21/A7_30") (pintype "bidirectional"))
    )
    (net (code "96") (name "unconnected-(U$2B-D22{slash}A8-Pad29)") (class "Default")
      (node (ref "U$2") (pin "29") (pinfunction "D22/A8_29") (pintype "bidirectional"))
    )
    (net (code "97") (name "unconnected-(U$2B-D23{slash}A9-Pad28)") (class "Default")
      (node (ref "U$2") (pin "28") (pinfunction "D23/A9_28") (pintype "bidirectional"))
    )
    (net (code "98") (name "unconnected-(U$2C-D24-Pad16)") (class "Default")
      (node (ref "U$2") (pin "16") (pinfunction "D24_16") (pintype "bidirectional"))
    )
    (net (code "99") (name "unconnected-(U$2C-D25-Pad17)") (class "Default")
      (node (ref "U$2") (pin "17") (pinfunction "D25_17") (pintype "bidirectional"))
    )
    (net (code "100") (name "unconnected-(U$2C-D26-Pad18)") (class "Default")
      (node (ref "U$2") (pin "18") (pinfunction "D26_18") (pintype "bidirectional"))
    )
    (net (code "101") (name "unconnected-(U$2C-D27-Pad19)") (class "Default")
      (node (ref "U$2") (pin "19") (pinfunction "D27_19") (pintype "bidirectional"))
    )
    (net (code "102") (name "unconnected-(U$2C-D28-Pad20)") (class "Default")
      (node (ref "U$2") (pin "20") (pinfunction "D28_20") (pintype "bidirectional"))
    )
    (net (code "103") (name "unconnected-(U$2C-D29-Pad21)") (class "Default")
      (node (ref "U$2") (pin "21") (pinfunction "D29_21") (pintype "bidirectional"))
    )
    (net (code "104") (name "unconnected-(U$2C-D30-Pad22)") (class "Default")
      (node (ref "U$2") (pin "22") (pinfunction "D30_22") (pintype "bidirectional"))
    )
    (net (code "105") (name "unconnected-(U$2C-D31{slash}A12-Pad23)") (class "Default")
      (node (ref "U$2") (pin "23") (pinfunction "D31/A12_23") (pintype "bidirectional"))
    )
    (net (code "106") (name "unconnected-(U$2C-D32{slash}A13-Pad24)") (class "Default")
      (node (ref "U$2") (pin "24") (pinfunction "D32/A13_24") (pintype "bidirectional"))
    )
    (net (code "107") (name "unconnected-(U$2C-D33{slash}A14-Pad48)") (class "Default")
      (node (ref "U$2") (pin "48") (pinfunction "D33/A14_48") (pintype "bidirectional"))
    )
    (net (code "108") (name "unconnected-(U$2C-D34{slash}A15-Pad47)") (class "Default")
      (node (ref "U$2") (pin "47") (pinfunction "D34/A15_47") (pintype "bidirectional"))
    )
    (net (code "109") (name "unconnected-(U$2C-D35{slash}A16-Pad46)") (class "Default")
      (node (ref "U$2") (pin "46") (pinfunction "D35/A16_46") (pintype "bidirectional"))
    )
    (net (code "110") (name "unconnected-(U$2C-D36{slash}A17-Pad45)") (class "Default")
      (node (ref "U$2") (pin "45") (pinfunction "D36/A17_45") (pintype "bidirectional"))
    )
    (net (code "111") (name "unconnected-(U$2C-D37{slash}A18-Pad44)") (class "Default")
      (node (ref "U$2") (pin "44") (pinfunction "D37/A18_44") (pintype "bidirectional"))
    )
    (net (code "112") (name "unconnected-(U$2C-D38{slash}A19-Pad43)") (class "Default")
      (node (ref "U$2") (pin "43") (pinfunction "D38/A19_43") (pintype "bidirectional"))
    )
    (net (code "113") (name "unconnected-(U$2C-D39{slash}A20-Pad42)") (class "Default")
      (node (ref "U$2") (pin "42") (pinfunction "D39/A20_42") (pintype "bidirectional"))
    )
    (net (code "114") (name "unconnected-(U$2C-DAC0-Pad41)") (class "Default")
      (node (ref "U$2") (pin "41") (pinfunction "DAC0_41") (pintype "bidirectional"))
    )
    (net (code "115") (name "unconnected-(U$2C-DAC1-Pad40)") (class "Default")
      (node (ref "U$2") (pin "40") (pinfunction "DAC1_40") (pintype "bidirectional"))
    )
  )
)
